# Sheet1_FL.net
KiCad netlist of a schematic drawn in Altium Designer
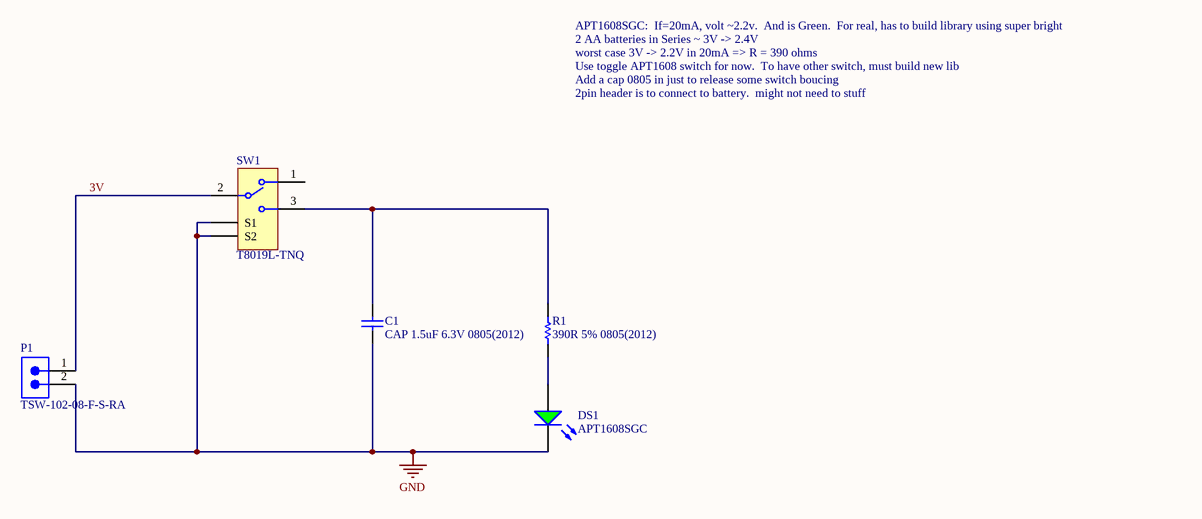
[diagram p0: Sheet1_FL.SchDoc]

(export (version "E")
  (design (tool "Eeschema 10.0.6"))
  (components
    (comp (ref "C1")
      (value "CAP 1.5uF 6.3V 0805(2012)")
      (footprint "CAPC0805(2012)100_M")
      (description "CAP 1.5uF 6.3V ±20% 0805 (2012 Metric) Thickness 1mm SMD")
      (fields (field (name "TOLERANCE") "Â±20%"))
      (libsource (lib "Altium Content Vault") (part "CAP"))
    )
    (comp (ref "DS1")
      (value "APT1608SGC")
      (footprint "KING-APT1608SGC_V")
      (description "Super Bright Green LED, 62.5 mW, 25 mA, -40 to 85 degC, 2-Pin SMD, RoHS, Tape and Reel")
      (fields (field (name "MANUFACTURER") "Kingbright"))
      (libsource (lib "Altium Content Vault") (part "LED-GREEN-AK-2"))
    )
    (comp (ref "P1")
      (value "TSW-102-08-F-S-RA")
      (footprint "SMTC-TSW-102-08-X-S-RA")
      (fields (field (name "MANUFACTURER") "Samtec"))
      (libsource (lib "Altium Content Vault") (part "SMTC-TSW-102-X-X-S-X"))
    )
    (comp (ref "R1")
      (value "390R 5% 0805(2012)")
      (footprint "RESC0805(2012)_N")
      (description "390R 0.125W 5% 0805 (2012 Metric)  SMD")
      (fields (field (name "POWER") "0.125 W") (field (name "TOLERANCE") "5 %"))
      (libsource (lib "Altium Content Vault") (part "RES"))
    )
    (comp (ref "SW1")
      (value "T8019L-TNQ")
      (footprint "SALE-T8019L-5_V")
      (description "Toggle Switch, SPDT, Through Hole, 3 Terminals")
      (fields (field (name "MANUFACTURER") "Salecom Electronics"))
      (libsource (lib "Altium Content Vault") (part "SALE-T8019L-5"))
    )
  )
  (nets
    (net (code "1") (name "/3V") (class "Default")
      (node (ref "P1") (pin "1") (pinfunction "1_1") (pintype "passive"))
      (node (ref "SW1") (pin "2") (pintype "passive"))
    )
    (net (code "2") (name "GND") (class "Default")
      (node (ref "C1") (pin "1") (pinfunction "1_1") (pintype "passive"))
      (node (ref "DS1") (pin "2") (pinfunction "K_2") (pintype "passive"))
      (node (ref "P1") (pin "2") (pinfunction "2_2") (pintype "passive"))
      (node (ref "SW1") (pin "S1") (pinfunction "S1_S1") (pintype "passive"))
      (node (ref "SW1") (pin "S2") (pinfunction "S2_S2") (pintype "passive"))
    )
    (net (code "3") (name "Net-(C1-Pad2)") (class "Default")
      (node (ref "C1") (pin "2") (pinfunction "2_2") (pintype "passive"))
      (node (ref "R1") (pin "2") (pinfunction "2_2") (pintype "passive"))
      (node (ref "SW1") (pin "3") (pintype "passive"))
    )
    (net (code "4") (name "Net-(DS1-A)") (class "Default")
      (node (ref "DS1") (pin "1") (pinfunction "A_1") (pintype "passive"))
      (node (ref "R1") (pin "1") (pinfunction "1_1") (pintype "passive"))
    )
    (net (code "5") (name "unconnected-(SW1-Pad1)") (class "Default")
      (node (ref "SW1") (pin "1") (pintype "passive"))
    )
  )
)
